# CarettaCellModule.net
KiCad netlist of a schematic drawn in Altium Designer
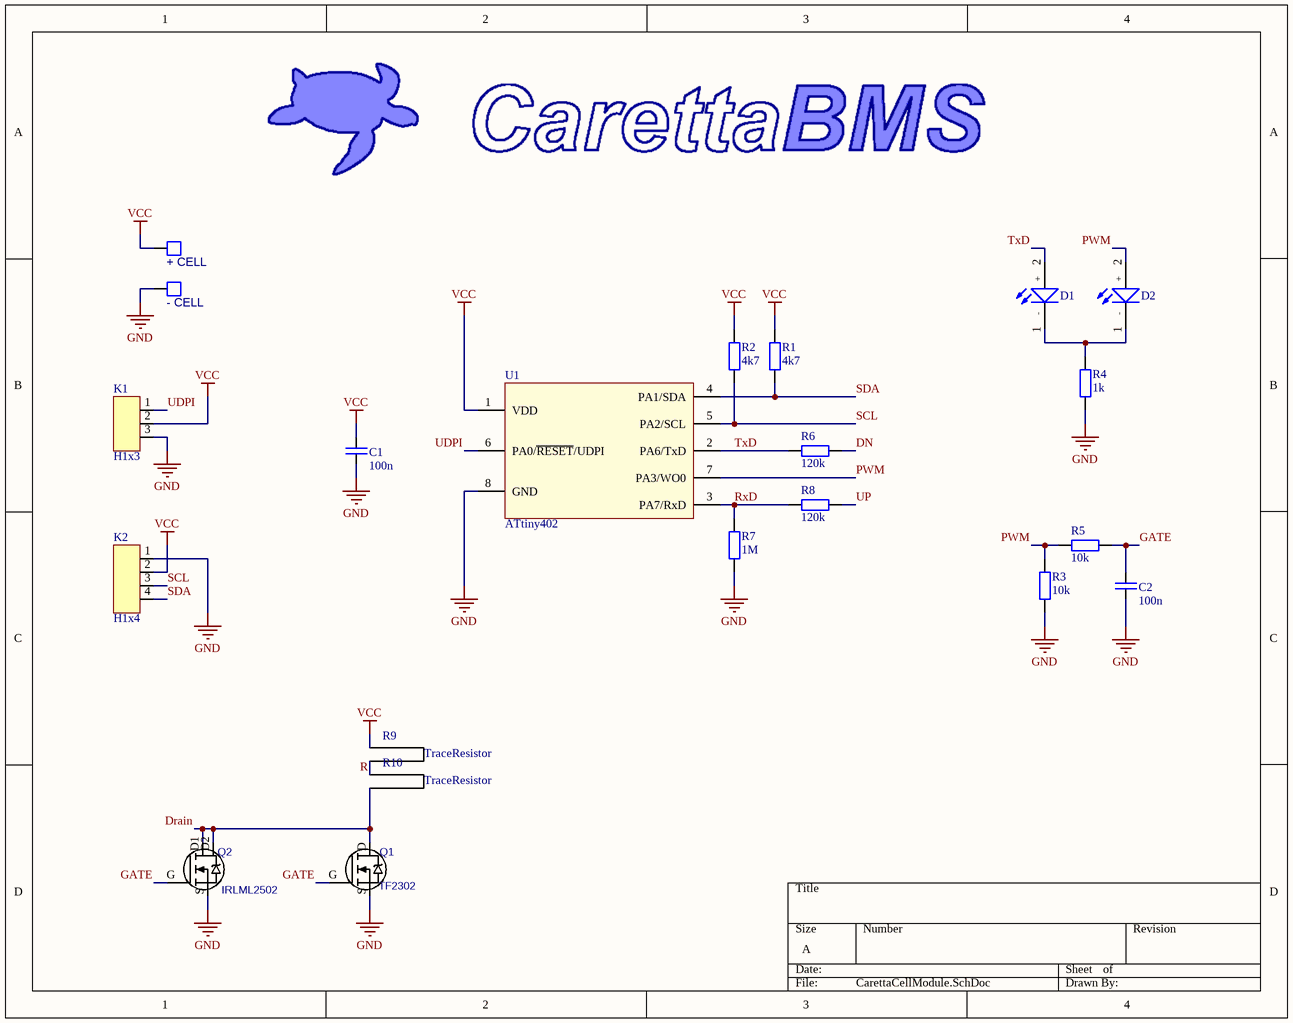
[diagram p0: CarettaCellModule.SchDoc]

(export (version "E")
  (design (tool "Eeschema 10.0.6"))
  (components
    (comp (ref "+ CELL") (value "PAD") (footprint "PAD") (libsource (lib "CarretaOpenBMS") (part "PAD")))
    (comp (ref "- CELL") (value "PAD") (footprint "PAD") (libsource (lib "CarretaOpenBMS") (part "PAD")))
    (comp (ref "C1")
      (value "100n")
      (footprint "C1608_0603I_N")
      (description "Capacitor")
      (libsource (lib "CarretaOpenBMS") (part "C"))
    )
    (comp (ref "C2")
      (value "100n")
      (footprint "C1608_0603I_N")
      (description "Capacitor")
      (libsource (lib "CarretaOpenBMS") (part "C"))
    )
    (comp (ref "D1")
      (value "LED")
      (footprint "LED1608_0603I_N")
      (libsource (lib "CarretaOpenBMS") (part "LED"))
    )
    (comp (ref "D2")
      (value "LED")
      (footprint "LED1608_0603I_N")
      (libsource (lib "CarretaOpenBMS") (part "LED"))
    )
    (comp (ref "K1")
      (value "H1x3")
      (footprint "H1x3")
      (description "Header 1x3 (male)")
      (libsource (lib "CarretaOpenBMS") (part "H1x3"))
    )
    (comp (ref "K2")
      (value "H1x4")
      (footprint "H1x4")
      (description "Header 1x4 (male)")
      (libsource (lib "CarretaOpenBMS") (part "H1x4"))
    )
    (comp (ref "Q1")
      (value "TF2302")
      (footprint "SOT23-3_N")
      (description "N-ch, Vdss=60V, Id=115mA, Rdson=2R")
      (libsource (lib "CarretaOpenBMS") (part "2N7002"))
    )
    (comp (ref "Q2")
      (value "IRLML2502")
      (footprint "SOT223_L")
      (description "BSP603S2L")
      (libsource (lib "CarretaOpenBMS") (part "BSP603S2L"))
    )
    (comp (ref "R1")
      (value "4k7")
      (footprint "R1608_0603I_N")
      (description "R")
      (libsource (lib "CarretaOpenBMS") (part "R"))
    )
    (comp (ref "R2")
      (value "4k7")
      (footprint "R1608_0603I_N")
      (description "R")
      (libsource (lib "CarretaOpenBMS") (part "R"))
    )
    (comp (ref "R3")
      (value "10k")
      (footprint "R1608_0603I_N")
      (description "R")
      (libsource (lib "CarretaOpenBMS") (part "R"))
    )
    (comp (ref "R4")
      (value "1k")
      (footprint "R1608_0603I_N")
      (description "R")
      (libsource (lib "CarretaOpenBMS") (part "R"))
    )
    (comp (ref "R5")
      (value "10k")
      (footprint "R1608_0603I_N")
      (description "R")
      (libsource (lib "CarretaOpenBMS") (part "R"))
    )
    (comp (ref "R6")
      (value "120k")
      (footprint "R1608_0603I_N")
      (description "R")
      (libsource (lib "CarretaOpenBMS") (part "R"))
    )
    (comp (ref "R7")
      (value "1M")
      (footprint "R1608_0603I_N")
      (description "R")
      (libsource (lib "CarretaOpenBMS") (part "R"))
    )
    (comp (ref "R8")
      (value "120k")
      (footprint "R1608_0603I_N")
      (description "R")
      (libsource (lib "CarretaOpenBMS") (part "R"))
    )
    (comp (ref "R9")
      (value "TraceResistor")
      (footprint "NetTie")
      (libsource (lib "CarretaOpenBMS") (part "TraceResistor"))
    )
    (comp (ref "R10")
      (value "TraceResistor")
      (footprint "NetTie")
      (libsource (lib "CarretaOpenBMS") (part "TraceResistor"))
    )
    (comp (ref "U1")
      (value "ATtiny402")
      (footprint "ATtiny402-SSFR")
      (libsource (lib "CarretaOpenBMS") (part "ATtiny402"))
    )
  )
  (nets
    (net (code "1") (name "/DN") (class "Default") (node (ref "R6") (pin "2") (pintype "passive")))
    (net (code "2") (name "/Drain") (class "Default")
      (node (ref "Q1") (pin "D") (pinfunction "D_D") (pintype "passive"))
      (node (ref "Q2") (pin "D1") (pinfunction "D_D1") (pintype "passive"))
      (node (ref "Q2") (pin "D2") (pinfunction "D_D2") (pintype "passive"))
      (node (ref "R10") (pin "2") (pinfunction "2_2") (pintype "passive"))
    )
    (net (code "3") (name "/GATE") (class "Default")
      (node (ref "C2") (pin "1") (pinfunction "1_1") (pintype "passive"))
      (node (ref "Q1") (pin "G") (pinfunction "G_G") (pintype "passive"))
      (node (ref "Q2") (pin "G") (pinfunction "G_G") (pintype "passive"))
      (node (ref "R5") (pin "2") (pintype "passive"))
    )
    (net (code "4") (name "/PWM") (class "Default")
      (node (ref "D2") (pin "2") (pinfunction "+_2") (pintype "passive"))
      (node (ref "R3") (pin "1") (pintype "passive"))
      (node (ref "R5") (pin "1") (pintype "passive"))
      (node (ref "U1") (pin "7") (pinfunction "PA3/WO0_7") (pintype "passive"))
    )
    (net (code "5") (name "/R") (class "Default")
      (node (ref "R10") (pin "1") (pinfunction "1_1") (pintype "passive"))
      (node (ref "R9") (pin "2") (pinfunction "2_2") (pintype "passive"))
    )
    (net (code "6") (name "/RxD") (class "Default")
      (node (ref "R7") (pin "1") (pintype "passive"))
      (node (ref "R8") (pin "1") (pintype "passive"))
      (node (ref "U1") (pin "3") (pinfunction "PA7/RxD_3") (pintype "passive"))
    )
    (net (code "7") (name "/SCL") (class "Default")
      (node (ref "K2") (pin "3") (pinfunction "3_3") (pintype "passive"))
      (node (ref "R2") (pin "2") (pintype "passive"))
      (node (ref "U1") (pin "5") (pinfunction "PA2/SCL_5") (pintype "passive"))
    )
    (net (code "8") (name "/SDA") (class "Default")
      (node (ref "K2") (pin "4") (pinfunction "4_4") (pintype "passive"))
      (node (ref "R1") (pin "2") (pintype "passive"))
      (node (ref "U1") (pin "4") (pinfunction "PA1/SDA_4") (pintype "passive"))
    )
    (net (code "9") (name "/TxD") (class "Default")
      (node (ref "D1") (pin "2") (pinfunction "+_2") (pintype "passive"))
      (node (ref "R6") (pin "1") (pintype "passive"))
      (node (ref "U1") (pin "2") (pinfunction "PA6/TxD_2") (pintype "passive"))
    )
    (net (code "10") (name "/UDPI") (class "Default")
      (node (ref "K1") (pin "1") (pinfunction "1_1") (pintype "passive"))
      (node (ref "U1") (pin "6") (pinfunction "PA0/~{RESET}/UDPI_6") (pintype "passive"))
    )
    (net (code "11") (name "/UP") (class "Default") (node (ref "R8") (pin "2") (pintype "passive")))
    (net (code "12") (name "GND") (class "Default")
      (node (ref "- CELL") (pin "1") (pinfunction "1_1") (pintype "passive"))
      (node (ref "C1") (pin "2") (pinfunction "2_2") (pintype "passive"))
      (node (ref "C2") (pin "2") (pinfunction "2_2") (pintype "passive"))
      (node (ref "K1") (pin "3") (pinfunction "3_3") (pintype "passive"))
      (node (ref "K2") (pin "1") (pinfunction "1_1") (pintype "passive"))
      (node (ref "Q1") (pin "S") (pinfunction "S_S") (pintype "passive"))
      (node (ref "Q2") (pin "S") (pinfunction "S_S") (pintype "passive"))
      (node (ref "R3") (pin "2") (pintype "passive"))
      (node (ref "R4") (pin "2") (pintype "passive"))
      (node (ref "R7") (pin "2") (pintype "passive"))
      (node (ref "U1") (pin "8") (pinfunction "GND_8") (pintype "passive"))
    )
    (net (code "13") (name "Net-(D1--)") (class "Default")
      (node (ref "D1") (pin "1") (pinfunction "-_1") (pintype "passive"))
      (node (ref "D2") (pin "1") (pinfunction "-_1") (pintype "passive"))
      (node (ref "R4") (pin "1") (pintype "passive"))
    )
    (net (code "14") (name "VCC") (class "Default")
      (node (ref "+ CELL") (pin "1") (pinfunction "1_1") (pintype "passive"))
      (node (ref "C1") (pin "1") (pinfunction "1_1") (pintype "passive"))
      (node (ref "K1") (pin "2") (pinfunction "2_2") (pintype "passive"))
      (node (ref "K2") (pin "2") (pinfunction "2_2") (pintype "passive"))
      (node (ref "R1") (pin "1") (pintype "passive"))
      (node (ref "R2") (pin "1") (pintype "passive"))
      (node (ref "R9") (pin "1") (pinfunction "1_1") (pintype "passive"))
      (node (ref "U1") (pin "1") (pinfunction "VDD_1") (pintype "passive"))
    )
  )
)
